# 1_Channel_Opto_Relay.net
KiCad netlist of a schematic drawn in Altium Designer
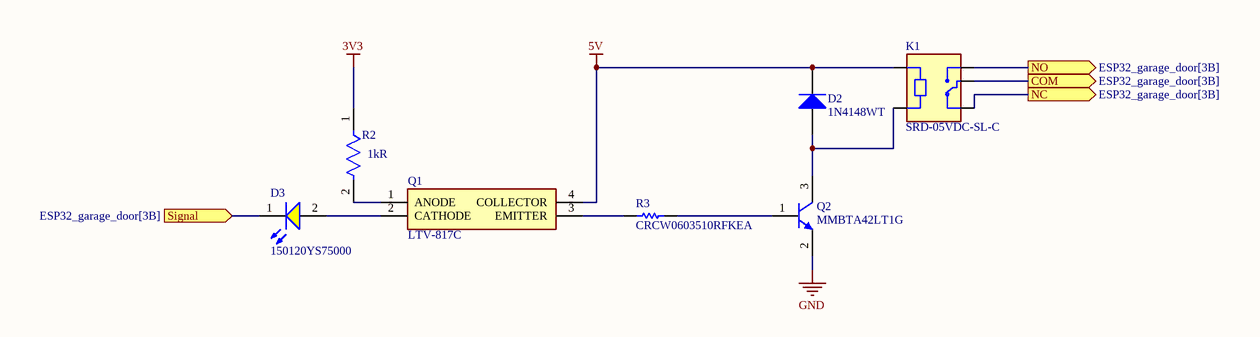
[diagram p0: 1_Channel_Opto_Relay.SchDoc]

(export (version "E")
  (design (tool "Eeschema 10.0.6"))
  (components
    (comp (ref "D2")
      (value "1N4148WT")
      (footprint "FAIR-SOD-523F-2_V")
      (description "High Conductance Fast Switching Diode, 75 V, -55 to 150 degC, 2-Pin SOD523F, RoHS")
      (fields (field (name "MANUFACTURER") "Fairchild Semiconductor"))
      (libsource (lib "Altium Content Vault") (part "FAIR-D_K1A2-2"))
    )
    (comp (ref "D3")
      (value "150120YS75000")
      (footprint "WL-SMCW_1206_150120xx75000")
      (description "Led, Yellow, 590 Nm, 2 V, 30 Ma, 120 Mcd Rohs Compliant: Yes")
      (libsource (lib "Altium Content Vault") (part "LED_Yellow_2A-1K"))
    )
    (comp (ref "K1")
      (value "SRD-05VDC-SL-C")
      (footprint "RELAY_SRD-05VDC-SL-C")
      (fields (field (name "MF") "Songle Relay"))
      (libsource (lib "Lukas Jensch") (part "SRD-05VDC-SL-C"))
    )
    (comp (ref "Q1")
      (value "LTV-817C")
      (footprint "SamacSys:DIP762W60P254L460H450Q4N")
      (description "Phototransistor")
      (fields (field (name "MOUSER PART NUMBER") "859-LTV-817C"))
      (libsource (lib "*") (part "LTV-817C"))
    )
    (comp (ref "Q2")
      (value "MMBTA42LT1G")
      (footprint "ONSC-SOT-23-3-318-08_V")
      (description "High Voltage Transistor, NPN Silicon, 3-Pin SOT-23, Pb-Free, Tape and Reel")
      (fields (field (name "MANUFACTURER") "On Semiconductor"))
      (libsource (lib "Altium Content Vault") (part "ONSC-NPN-B1E2C3-3"))
    )
    (comp (ref "R2")
      (value "AC0603FR-071KL")
      (footprint "FP-AC0603-IPC_B")
      (description "RES 1kΩ 1.00% 0.1W 0603")
      (fields (field (name "TOLERANCE") "1%") (field (name "RESISTANCE") "1kR"))
      (libsource (lib "Altium Content Vault") (part "1029c3af85768c4190bb7ad29bc67b5"))
    )
    (comp (ref "R3")
      (value "CRCW0603510RFKEA")
      (footprint "RESC1609X50X30NL10T20")
      (fields (field (name "MANUFACTURER") "Vishay Dale"))
      (libsource (lib "Altium Content Vault") (part "RES"))
    )
  )
  (nets
    (net (code "1") (name "/COM") (class "Default")
      (node (ref "K1") (pin "COM") (pinfunction "COM_COM") (pintype "passive"))
    )
    (net (code "2") (name "/NC") (class "Default")
      (node (ref "K1") (pin "NC") (pinfunction "NC_NC") (pintype "passive"))
    )
    (net (code "3") (name "/NO") (class "Default")
      (node (ref "K1") (pin "NO") (pinfunction "NO_NO") (pintype "passive"))
    )
    (net (code "4") (name "/Signal") (class "Default")
      (node (ref "D3") (pin "1") (pinfunction "K_1") (pintype "passive"))
    )
    (net (code "5") (name "3V3") (class "Default")
      (node (ref "R2") (pin "1") (pinfunction "1_1") (pintype "passive"))
    )
    (net (code "6") (name "5V") (class "Default")
      (node (ref "D2") (pin "1") (pinfunction "K_1") (pintype "passive"))
      (node (ref "K1") (pin "A1") (pinfunction "A1_A1") (pintype "passive"))
      (node (ref "Q1") (pin "4") (pinfunction "COLLECTOR_4") (pintype "passive"))
    )
    (net (code "7") (name "GND") (class "Default")
      (node (ref "Q2") (pin "2") (pinfunction "E_2") (pintype "passive"))
    )
    (net (code "8") (name "Net-(D2-A)") (class "Default")
      (node (ref "D2") (pin "2") (pinfunction "A_2") (pintype "passive"))
      (node (ref "K1") (pin "A2") (pinfunction "A2_A2") (pintype "passive"))
      (node (ref "Q2") (pin "3") (pinfunction "C_3") (pintype "passive"))
    )
    (net (code "9") (name "Net-(D3-A)") (class "Default")
      (node (ref "D3") (pin "2") (pinfunction "A_2") (pintype "passive"))
      (node (ref "Q1") (pin "2") (pinfunction "CATHODE_2") (pintype "passive"))
    )
    (net (code "10") (name "Net-(Q1-ANODE)") (class "Default")
      (node (ref "Q1") (pin "1") (pinfunction "ANODE_1") (pintype "passive"))
      (node (ref "R2") (pin "2") (pinfunction "2_2") (pintype "passive"))
    )
    (net (code "11") (name "Net-(Q1-EMITTER)") (class "Default")
      (node (ref "Q1") (pin "3") (pinfunction "EMITTER_3") (pintype "passive"))
      (node (ref "R3") (pin "1") (pinfunction "1_1") (pintype "passive"))
    )
    (net (code "12") (name "Net-(Q2-B)") (class "Default")
      (node (ref "Q2") (pin "1") (pinfunction "B_1") (pintype "passive"))
      (node (ref "R3") (pin "2") (pinfunction "2_2") (pintype "passive"))
    )
  )
)
